# Power_System.net
KiCad netlist of a schematic drawn in Altium Designer
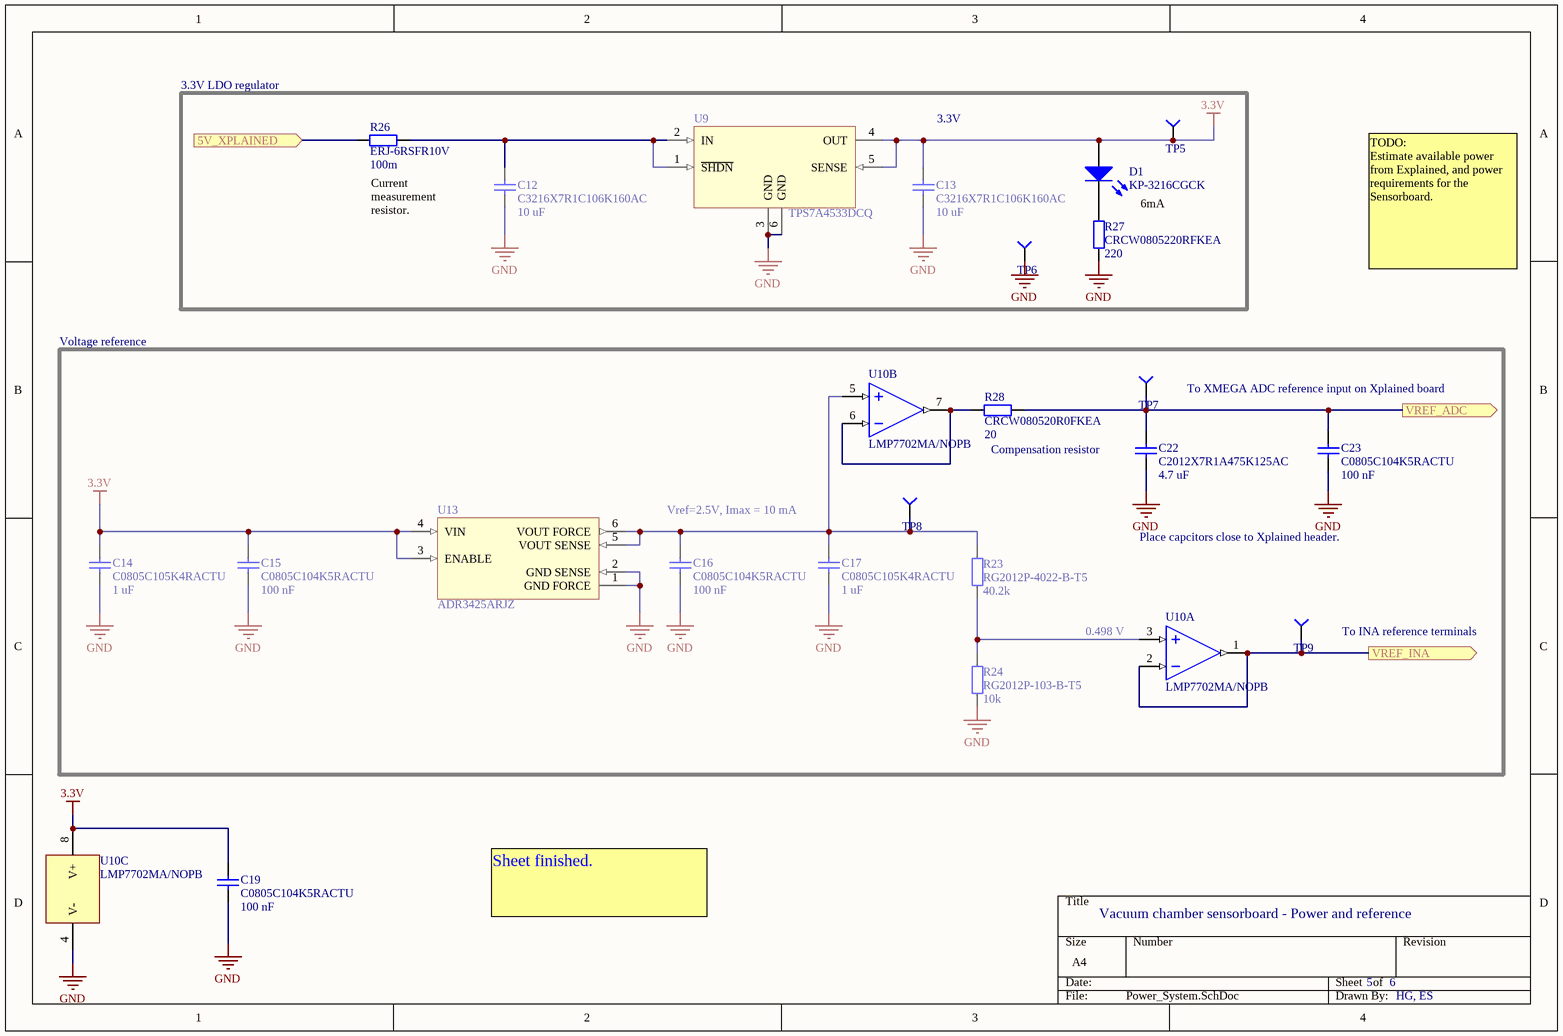
[diagram p0: Power_System.SchDoc]

(export (version "E")
  (design (tool "Eeschema 10.0.6"))
  (components
    (comp (ref "C12")
      (value "C3216X7R1C106K160AC")
      (footprint "Cap TDK1206")
      (description "Ceramic capacitor, X7R, 10%, 16V")
      (fields (field (name "MANUFACTURER") "TDK") (field (name "ALTIUM_VALUE") "10 uF"))
      (libsource (lib "EITlib") (part "C3216X7R1C106K160AC"))
    )
    (comp (ref "C13")
      (value "C3216X7R1C106K160AC")
      (footprint "Cap TDK1206")
      (description "Ceramic capacitor, X7R, 10%, 16V")
      (fields (field (name "MANUFACTURER") "TDK") (field (name "ALTIUM_VALUE") "10 uF"))
      (libsource (lib "EITlib") (part "C3216X7R1C106K160AC"))
    )
    (comp (ref "C14")
      (value "C0805C105K4RACTU")
      (footprint "Cap Kemet 0805")
      (description "Ceramic capacitor, X7R, 10%, 16V")
      (fields (field (name "MANUFACTURER") "Kemet") (field (name "ALTIUM_VALUE") "1 uF"))
      (libsource (lib "EITlib") (part "C0805C105K4RACTU"))
    )
    (comp (ref "C15")
      (value "C0805C104K5RACTU")
      (footprint "Cap Kemet 0805")
      (description "Ceramic capacitor, X7R, 10%, 50V")
      (fields (field (name "MANUFACTURER") "Kemet") (field (name "ALTIUM_VALUE") "100 nF"))
      (libsource (lib "EITlib") (part "C0805C104K5RACTU"))
    )
    (comp (ref "C16")
      (value "C0805C104K5RACTU")
      (footprint "Cap Kemet 0805")
      (description "Ceramic capacitor, X7R, 10%, 50V")
      (fields (field (name "MANUFACTURER") "Kemet") (field (name "ALTIUM_VALUE") "100 nF"))
      (libsource (lib "EITlib") (part "C0805C104K5RACTU"))
    )
    (comp (ref "C17")
      (value "C0805C105K4RACTU")
      (footprint "Cap Kemet 0805")
      (description "Ceramic capacitor, X7R, 10%, 16V")
      (fields (field (name "MANUFACTURER") "Kemet") (field (name "ALTIUM_VALUE") "1 uF"))
      (libsource (lib "EITlib") (part "C0805C105K4RACTU"))
    )
    (comp (ref "C19")
      (value "C0805C104K5RACTU")
      (footprint "Cap Kemet 0805")
      (description "Ceramic capacitor, X7R, 10%, 50V")
      (fields (field (name "MANUFACTURER") "Kemet") (field (name "ALTIUM_VALUE") "100 nF"))
      (libsource (lib "EITlib") (part "C0805C104K5RACTU"))
    )
    (comp (ref "C22")
      (value "C2012X7R1A475K125AC")
      (footprint "Cap TDK0805")
      (description "Ceramic capacitor, X7R, 10%, 10V")
      (fields (field (name "MANUFACTURER") "TDK") (field (name "ALTIUM_VALUE") "4.7 uF"))
      (libsource (lib "EITlib") (part "C2012X7R1A475K125AC"))
    )
    (comp (ref "C23")
      (value "C0805C104K5RACTU")
      (footprint "Cap Kemet 0805")
      (description "Ceramic capacitor, X7R, 10%, 50V")
      (fields (field (name "MANUFACTURER") "Kemet") (field (name "ALTIUM_VALUE") "100 nF"))
      (libsource (lib "EITlib") (part "C0805C104K5RACTU"))
    )
    (comp (ref "D1")
      (value "KP-3216CGCK")
      (footprint "Diode Kingbright")
      (description "Chip led lamp,green, 50mcd @ 20mA")
      (fields (field (name "MANUFACTURER") "Kingbright"))
      (libsource (lib "EITlib") (part "KP-3216CGCK"))
    )
    (comp (ref "R23")
      (value "RG2012P-4022-B-T5")
      (footprint "RES SSM 0805")
      (description "Thin film resistor, 0.1%, 100mW")
      (fields (field (name "MANUFACTURER") "Susumu") (field (name "ALTIUM_VALUE") "40.2k"))
      (libsource (lib "EITlib") (part "RG2012P-4022-B-T5"))
    )
    (comp (ref "R24")
      (value "RG2012P-103-B-T5")
      (footprint "RES SSM 0805")
      (description "Thin film resistor, 0.1%, 100mW")
      (fields (field (name "MANUFACTURER") "Susumu") (field (name "ALTIUM_VALUE") "10k"))
      (libsource (lib "EITlib") (part "RG2012P-103-B-T5"))
    )
    (comp (ref "R26")
      (value "ERJ-6RSFR10V")
      (footprint "Res panasonic0805")
      (description "Thick film resistor, 1%, 125mW")
      (fields (field (name "MANUFACTURER") "Panasonic") (field (name "ALTIUM_VALUE") "100m"))
      (libsource (lib "EITlib") (part "ERJ-6RSFR10V"))
    )
    (comp (ref "R27")
      (value "CRCW0805220RFKEA")
      (footprint "Res Vishay0805")
      (description "Thick film resistor, 1%, 125mW")
      (fields (field (name "MANUFACTURER") "Vishay") (field (name "ALTIUM_VALUE") "220"))
      (libsource (lib "EITlib") (part "CRCW0805220RFKEA"))
    )
    (comp (ref "R28")
      (value "CRCW080520R0FKEA")
      (footprint "Res Vishay0805")
      (description "Thick film resistor, 1%, 125mW")
      (fields (field (name "MANUFACTURER") "Vishay") (field (name "ALTIUM_VALUE") "20"))
      (libsource (lib "EITlib") (part "CRCW080520R0FKEA"))
    )
    (comp (ref "TP5")
      (value "Test_point")
      (footprint "Testpoint")
      (libsource (lib "EITlib") (part "Test_point"))
    )
    (comp (ref "TP6")
      (value "Test_point")
      (footprint "Testpoint")
      (libsource (lib "EITlib") (part "Test_point"))
    )
    (comp (ref "TP7")
      (value "Test_point")
      (footprint "Testpoint")
      (libsource (lib "EITlib") (part "Test_point"))
    )
    (comp (ref "TP8")
      (value "Test_point")
      (footprint "Testpoint")
      (libsource (lib "EITlib") (part "Test_point"))
    )
    (comp (ref "TP9")
      (value "Test_point")
      (footprint "Testpoint")
      (libsource (lib "EITlib") (part "Test_point"))
    )
    (comp (ref "U9")
      (value "TPS7A4533DCQ")
      (footprint "TPS7A4533DCQ")
      (description "LDO regulator, 3.3V, 1.5A")
      (fields (field (name "MANUFACTURER") "Texas Instruments"))
      (libsource (lib "EITlib") (part "TPS7A4533DCQ"))
    )
    (comp (ref "U10")
      (value "LMP7702MA/NOPB")
      (footprint "OPA2333AIDR")
      (description "Op. amp, dual, rail-to-rail, single supply")
      (libsource (lib "") (part "LMP7702MA/NOPB_1"))
    )
    (comp (ref "U13")
      (value "ADR3425ARJZ")
      (footprint "ADR3425")
      (description "Series voltage reference, 2.5V")
      (fields (field (name "MANUFACTURER") "Analog Devices"))
      (libsource (lib "EITlib") (part "ADR3425ARJZ"))
    )
  )
  (nets
    (net (code "1") (name "/5V_XPLAINED") (class "Default")
      (node (ref "R26") (pin "1") (pinfunction "1_1") (pintype "passive"))
    )
    (net (code "2") (name "/VREF_ADC") (class "Default")
      (node (ref "C22") (pin "2") (pinfunction "2_2") (pintype "passive"))
      (node (ref "C23") (pin "2") (pinfunction "2_2") (pintype "passive"))
      (node (ref "R28") (pin "2") (pinfunction "2_2") (pintype "passive"))
      (node (ref "TP7") (pin "0") (pinfunction "0_0") (pintype "passive"))
    )
    (net (code "3") (name "/VREF_INA") (class "Default")
      (node (ref "TP9") (pin "0") (pinfunction "0_0") (pintype "passive"))
      (node (ref "U10") (pin "1") (pinfunction "OUT_A_1") (pintype "output"))
      (node (ref "U10") (pin "2") (pinfunction "-IN_A_2") (pintype "input"))
    )
    (net (code "4") (name "3.3V") (class "Default")
      (node (ref "C13") (pin "2") (pinfunction "2_2") (pintype "passive"))
      (node (ref "C14") (pin "2") (pinfunction "2_2") (pintype "passive"))
      (node (ref "C15") (pin "2") (pinfunction "2_2") (pintype "passive"))
      (node (ref "C19") (pin "2") (pinfunction "2_2") (pintype "passive"))
      (node (ref "D1") (pin "1") (pinfunction "A_1") (pintype "passive"))
      (node (ref "TP5") (pin "0") (pinfunction "0_0") (pintype "passive"))
      (node (ref "U10") (pin "8") (pinfunction "V+_8") (pintype "power_in"))
      (node (ref "U13") (pin "3") (pinfunction "ENABLE_3") (pintype "input"))
      (node (ref "U13") (pin "4") (pinfunction "VIN_4") (pintype "input"))
      (node (ref "U9") (pin "4") (pinfunction "OUT_4") (pintype "power_in"))
      (node (ref "U9") (pin "5") (pinfunction "SENSE_5") (pintype "input"))
    )
    (net (code "5") (name "GND") (class "Default")
      (node (ref "C12") (pin "1") (pinfunction "1_1") (pintype "passive"))
      (node (ref "C13") (pin "1") (pinfunction "1_1") (pintype "passive"))
      (node (ref "C14") (pin "1") (pinfunction "1_1") (pintype "passive"))
      (node (ref "C15") (pin "1") (pinfunction "1_1") (pintype "passive"))
      (node (ref "C16") (pin "1") (pinfunction "1_1") (pintype "passive"))
      (node (ref "C17") (pin "1") (pinfunction "1_1") (pintype "passive"))
      (node (ref "C19") (pin "1") (pinfunction "1_1") (pintype "passive"))
      (node (ref "C22") (pin "1") (pinfunction "1_1") (pintype "passive"))
      (node (ref "C23") (pin "1") (pinfunction "1_1") (pintype "passive"))
      (node (ref "R24") (pin "1") (pinfunction "1_1") (pintype "passive"))
      (node (ref "R27") (pin "1") (pinfunction "1_1") (pintype "passive"))
      (node (ref "TP6") (pin "0") (pinfunction "0_0") (pintype "passive"))
      (node (ref "U10") (pin "4") (pinfunction "V-_4") (pintype "power_in"))
      (node (ref "U13") (pin "1") (pinfunction "GND_FORCE_1") (pintype "power_in"))
      (node (ref "U13") (pin "2") (pinfunction "GND_SENSE_2") (pintype "input"))
      (node (ref "U9") (pin "3") (pinfunction "GND_3") (pintype "power_in"))
      (node (ref "U9") (pin "6") (pinfunction "GND_6") (pintype "power_in"))
    )
    (net (code "6") (name "Net-(D1-K)") (class "Default")
      (node (ref "D1") (pin "2") (pinfunction "K_2") (pintype "passive"))
      (node (ref "R27") (pin "2") (pinfunction "2_2") (pintype "passive"))
    )
    (net (code "7") (name "Net-(U9-IN)") (class "Default")
      (node (ref "C12") (pin "2") (pinfunction "2_2") (pintype "passive"))
      (node (ref "R26") (pin "2") (pinfunction "2_2") (pintype "passive"))
      (node (ref "U9") (pin "1") (pinfunction "~{SHDN}_1") (pintype "input"))
      (node (ref "U9") (pin "2") (pinfunction "IN_2") (pintype "input"))
    )
    (net (code "8") (name "Net-(U10A-+IN_A)") (class "Default")
      (node (ref "R23") (pin "1") (pinfunction "1_1") (pintype "passive"))
      (node (ref "R24") (pin "2") (pinfunction "2_2") (pintype "passive"))
      (node (ref "U10") (pin "3") (pinfunction "+IN_A_3") (pintype "input"))
    )
    (net (code "9") (name "Net-(U10B-+IN_B)") (class "Default")
      (node (ref "C16") (pin "2") (pinfunction "2_2") (pintype "passive"))
      (node (ref "C17") (pin "2") (pinfunction "2_2") (pintype "passive"))
      (node (ref "R23") (pin "2") (pinfunction "2_2") (pintype "passive"))
      (node (ref "TP8") (pin "0") (pinfunction "0_0") (pintype "passive"))
      (node (ref "U10") (pin "5") (pinfunction "+IN_B_5") (pintype "input"))
      (node (ref "U13") (pin "5") (pinfunction "VOUT_SENSE_5") (pintype "input"))
      (node (ref "U13") (pin "6") (pinfunction "VOUT_FORCE_6") (pintype "output"))
    )
    (net (code "10") (name "Net-(U10B--IN_B)") (class "Default")
      (node (ref "R28") (pin "1") (pinfunction "1_1") (pintype "passive"))
      (node (ref "U10") (pin "6") (pinfunction "-IN_B_6") (pintype "input"))
      (node (ref "U10") (pin "7") (pinfunction "OUT_B_7") (pintype "output"))
    )
  )
)
